# PIC16F877_board.net
KiCad netlist of a schematic drawn in EAGLE
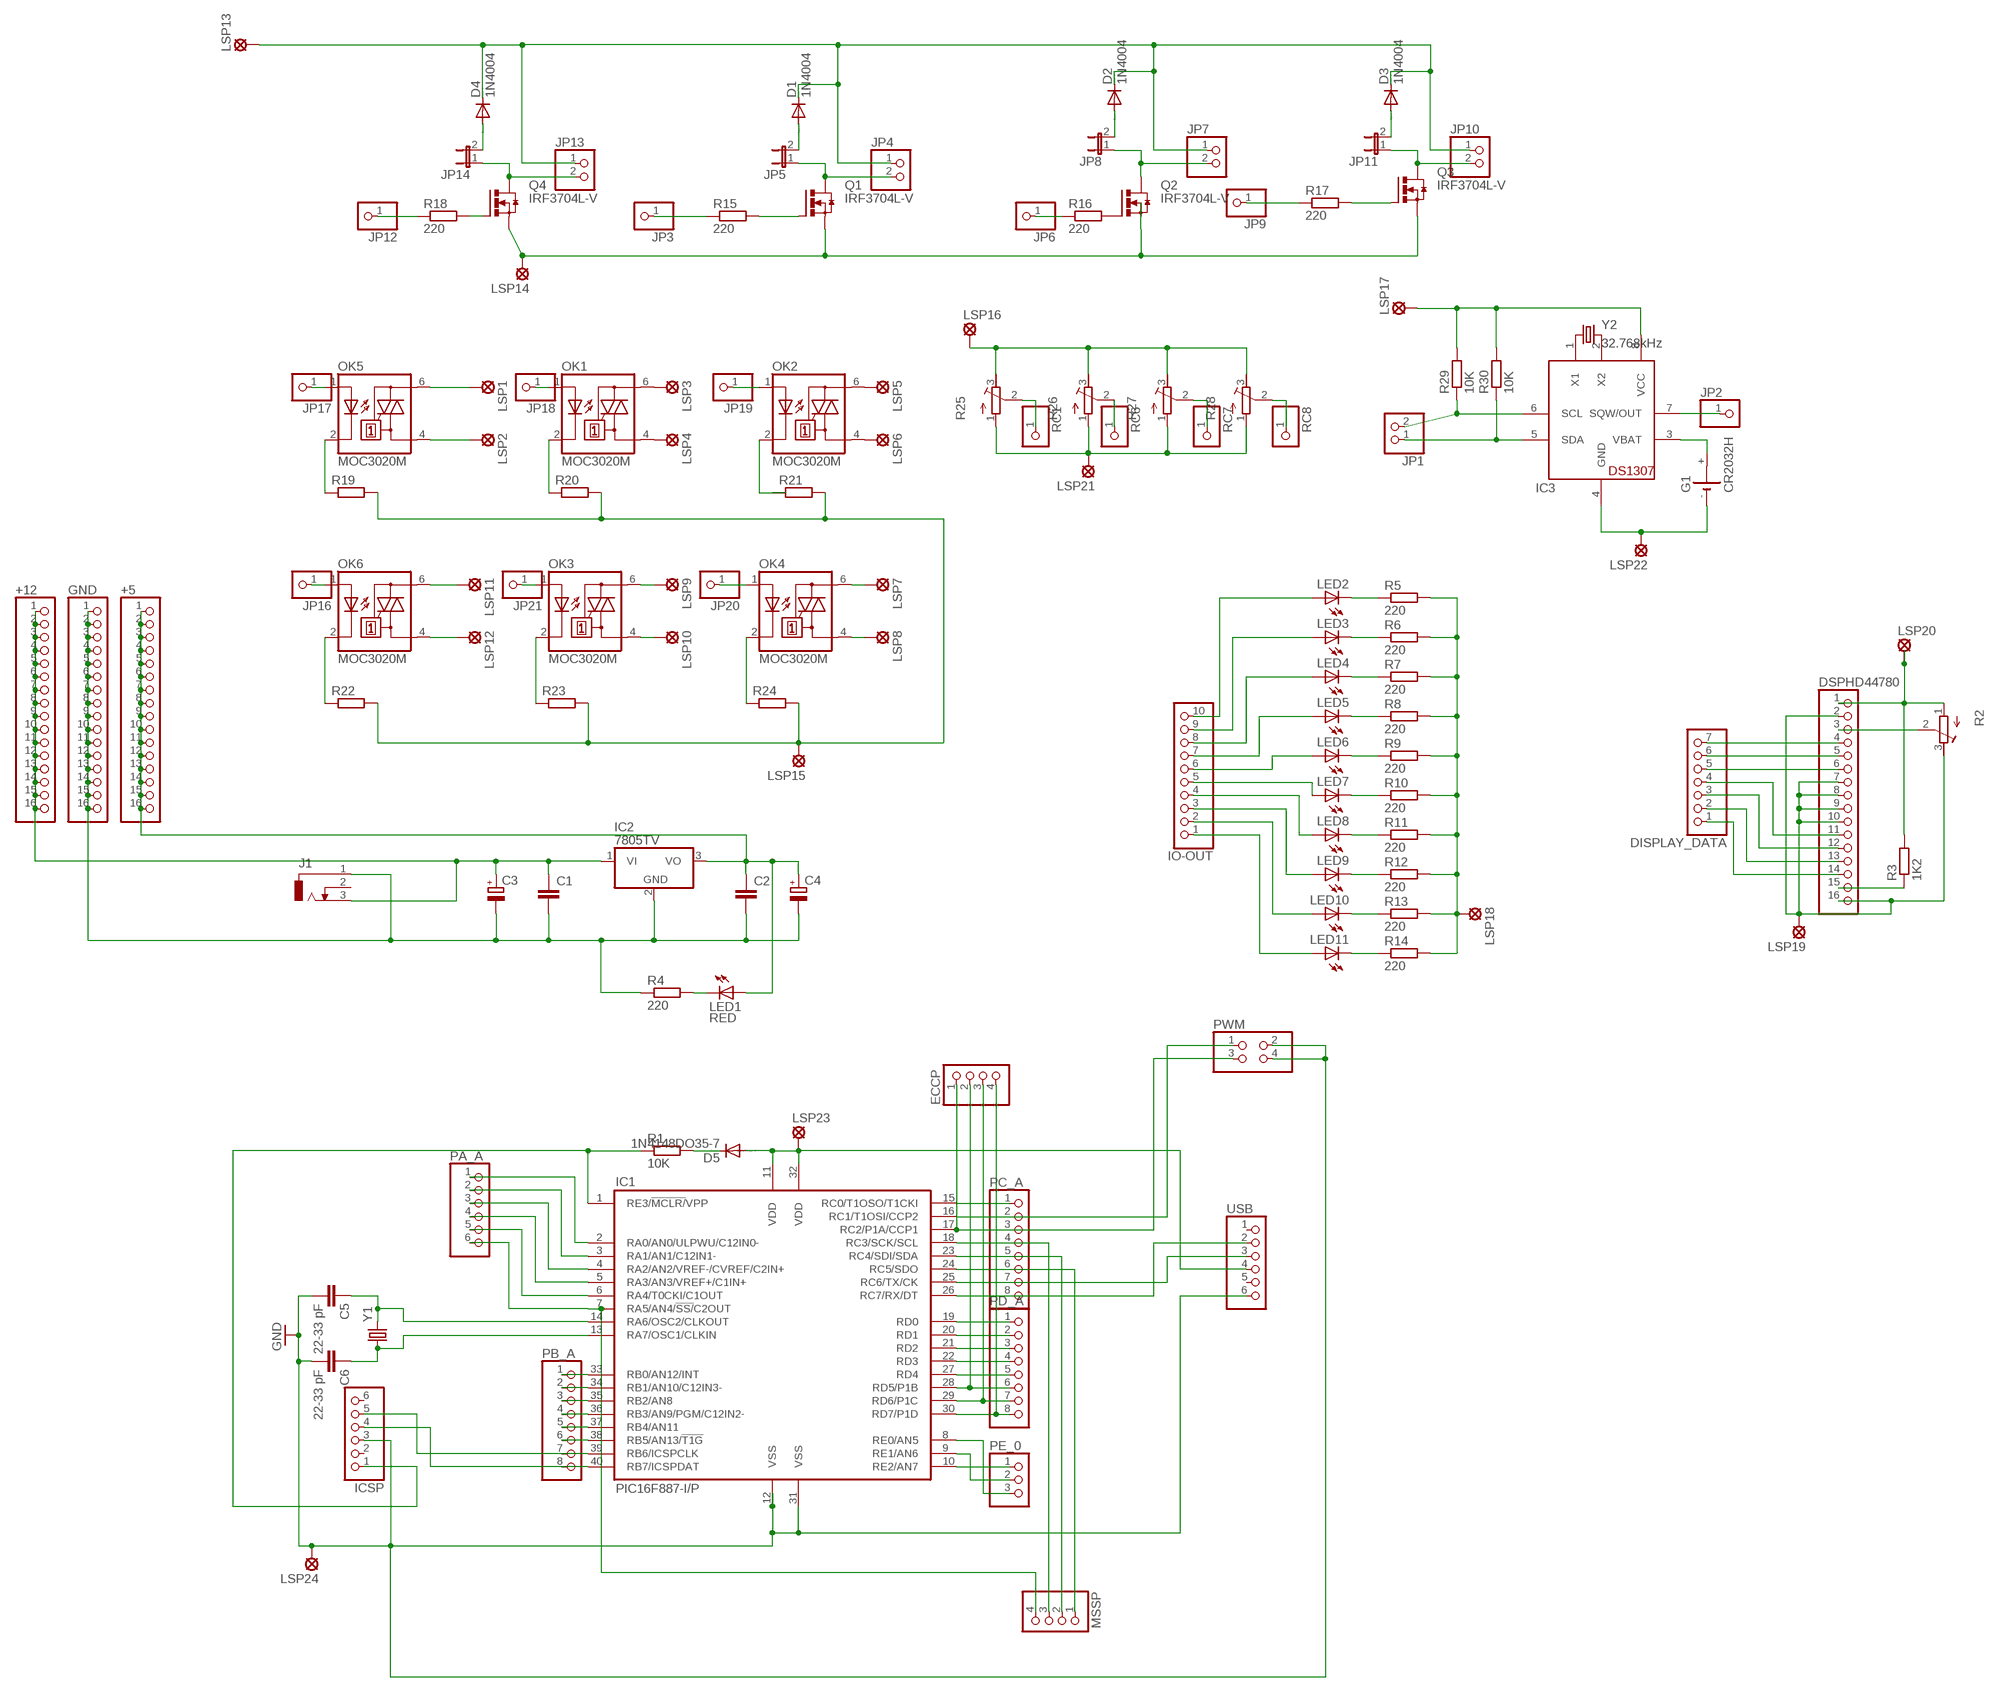
[diagram p0: schematic, sheet 1]

(export (version "E")
  (design (tool "Eeschema 10.0.6"))
  (components
    (comp (ref "+5")
      (value "PINHD-1X16")
      (footprint "eagle-import:1X16")
      (libsource (lib "eagle-import") (part "PINHD-1X16"))
    )
    (comp (ref "+12")
      (value "PINHD-1X16")
      (footprint "eagle-import:1X16")
      (libsource (lib "eagle-import") (part "PINHD-1X16"))
    )
    (comp (ref "C1")
      (value "C-EU050-025X075")
      (footprint "eagle-import:C050-025X075")
      (libsource (lib "eagle-import") (part "resistor_C-EU050-025X075"))
    )
    (comp (ref "C2")
      (value "C-EU050-025X075")
      (footprint "eagle-import:C050-025X075")
      (libsource (lib "eagle-import") (part "resistor_C-EU050-025X075"))
    )
    (comp (ref "C3")
      (value "CPOL-EUE2,5-6E")
      (footprint "eagle-import:E2,5-6E")
      (libsource (lib "eagle-import") (part "CPOL-EUE2,5-6E"))
    )
    (comp (ref "C4")
      (value "CPOL-EUE2,5-6E")
      (footprint "eagle-import:E2,5-6E")
      (libsource (lib "eagle-import") (part "CPOL-EUE2,5-6E"))
    )
    (comp (ref "C5")
      (value "22-33 pF")
      (footprint "eagle-import:C025-024X044")
      (libsource (lib "eagle-import") (part "C-EU025-024X044"))
    )
    (comp (ref "C6")
      (value "22-33 pF")
      (footprint "eagle-import:C025-024X044")
      (libsource (lib "eagle-import") (part "C-EU025-024X044"))
    )
    (comp (ref "D1")
      (value "1N4004")
      (footprint "eagle-import:DO41-10")
      (libsource (lib "eagle-import") (part "1N4004"))
    )
    (comp (ref "D2")
      (value "1N4004")
      (footprint "eagle-import:DO41-10")
      (libsource (lib "eagle-import") (part "1N4004"))
    )
    (comp (ref "D3")
      (value "1N4004")
      (footprint "eagle-import:DO41-10")
      (libsource (lib "eagle-import") (part "1N4004"))
    )
    (comp (ref "D4")
      (value "1N4004")
      (footprint "eagle-import:DO41-10")
      (libsource (lib "eagle-import") (part "1N4004"))
    )
    (comp (ref "D5")
      (value "1N4148DO35-7")
      (footprint "eagle-import:DO35-7")
      (libsource (lib "eagle-import") (part "1N4148DO35-7"))
    )
    (comp (ref "DISPLAY_DATA")
      (value "PINHD-1X7")
      (footprint "eagle-import:1X07")
      (libsource (lib "eagle-import") (part "PINHD-1X7"))
    )
    (comp (ref "DSPHD44780")
      (value "PINHD-1X16")
      (footprint "eagle-import:1X16")
      (libsource (lib "eagle-import") (part "PINHD-1X16"))
    )
    (comp (ref "ECCP")
      (value "PINHD-1X4")
      (footprint "eagle-import:1X04")
      (libsource (lib "eagle-import") (part "PINHD-1X4"))
    )
    (comp (ref "G1")
      (value "CR2032H")
      (footprint "eagle-import:CR2032H")
      (libsource (lib "eagle-import") (part "CR2032H"))
    )
    (comp (ref "GND")
      (value "PINHD-1X16")
      (footprint "eagle-import:1X16")
      (libsource (lib "eagle-import") (part "PINHD-1X16"))
    )
    (comp (ref "IC1")
      (value "PIC16F887-I/P")
      (footprint "eagle-import:DIL40")
      (libsource (lib "eagle-import") (part "PIC16F887-I/P"))
    )
    (comp (ref "IC2")
      (value "7805TV")
      (footprint "eagle-import:TO220V")
      (libsource (lib "eagle-import") (part "78TV05"))
    )
    (comp (ref "IC3")
      (value "DS1307")
      (footprint "eagle-import:DIL08")
      (libsource (lib "eagle-import") (part "DS1307"))
    )
    (comp (ref "ICSP")
      (value "PINHD-1X6")
      (footprint "eagle-import:1X06")
      (libsource (lib "eagle-import") (part "PINHD-1X6"))
    )
    (comp (ref "IO-OUT")
      (value "PINHD-1X10")
      (footprint "eagle-import:1X10")
      (libsource (lib "eagle-import") (part "PINHD-1X10"))
    )
    (comp (ref "J1")
      (value "DCJ0303")
      (footprint "eagle-import:DCJ0303")
      (libsource (lib "eagle-import") (part "DCJ0303"))
    )
    (comp (ref "JP1")
      (value "PINHD-1X2")
      (footprint "eagle-import:1X02")
      (libsource (lib "eagle-import") (part "PINHD-1X2"))
    )
    (comp (ref "JP2")
      (value "PINHD-1X1")
      (footprint "eagle-import:1X01")
      (libsource (lib "eagle-import") (part "PINHD-1X1"))
    )
    (comp (ref "JP3")
      (value "PINHD-1X1")
      (footprint "eagle-import:1X01")
      (libsource (lib "eagle-import") (part "PINHD-1X1"))
    )
    (comp (ref "JP4")
      (value "PINHD-1X2")
      (footprint "eagle-import:1X02")
      (libsource (lib "eagle-import") (part "PINHD-1X2"))
    )
    (comp (ref "JP5")
      (value "JP1E")
      (footprint "eagle-import:JP1")
      (libsource (lib "eagle-import") (part "JP1E"))
    )
    (comp (ref "JP6")
      (value "PINHD-1X1")
      (footprint "eagle-import:1X01")
      (libsource (lib "eagle-import") (part "PINHD-1X1"))
    )
    (comp (ref "JP7")
      (value "PINHD-1X2")
      (footprint "eagle-import:1X02")
      (libsource (lib "eagle-import") (part "PINHD-1X2"))
    )
    (comp (ref "JP8")
      (value "JP1E")
      (footprint "eagle-import:JP1")
      (libsource (lib "eagle-import") (part "JP1E"))
    )
    (comp (ref "JP9")
      (value "PINHD-1X1")
      (footprint "eagle-import:1X01")
      (libsource (lib "eagle-import") (part "PINHD-1X1"))
    )
    (comp (ref "JP10")
      (value "PINHD-1X2")
      (footprint "eagle-import:1X02")
      (libsource (lib "eagle-import") (part "PINHD-1X2"))
    )
    (comp (ref "JP11")
      (value "JP1E")
      (footprint "eagle-import:JP1")
      (libsource (lib "eagle-import") (part "JP1E"))
    )
    (comp (ref "JP12")
      (value "PINHD-1X1")
      (footprint "eagle-import:1X01")
      (libsource (lib "eagle-import") (part "PINHD-1X1"))
    )
    (comp (ref "JP13")
      (value "PINHD-1X2")
      (footprint "eagle-import:1X02")
      (libsource (lib "eagle-import") (part "PINHD-1X2"))
    )
    (comp (ref "JP14")
      (value "JP1E")
      (footprint "eagle-import:JP1")
      (libsource (lib "eagle-import") (part "JP1E"))
    )
    (comp (ref "JP16")
      (value "PINHD-1X1")
      (footprint "eagle-import:1X01")
      (libsource (lib "eagle-import") (part "PINHD-1X1"))
    )
    (comp (ref "JP17")
      (value "PINHD-1X1")
      (footprint "eagle-import:1X01")
      (libsource (lib "eagle-import") (part "PINHD-1X1"))
    )
    (comp (ref "JP18")
      (value "PINHD-1X1")
      (footprint "eagle-import:1X01")
      (libsource (lib "eagle-import") (part "PINHD-1X1"))
    )
    (comp (ref "JP19")
      (value "PINHD-1X1")
      (footprint "eagle-import:1X01")
      (libsource (lib "eagle-import") (part "PINHD-1X1"))
    )
    (comp (ref "JP20")
      (value "PINHD-1X1")
      (footprint "eagle-import:1X01")
      (libsource (lib "eagle-import") (part "PINHD-1X1"))
    )
    (comp (ref "JP21")
      (value "PINHD-1X1")
      (footprint "eagle-import:1X01")
      (libsource (lib "eagle-import") (part "PINHD-1X1"))
    )
    (comp (ref "LED1")
      (value "RED")
      (footprint "eagle-import:LED5MM")
      (libsource (lib "eagle-import") (part "LED5MM"))
    )
    (comp (ref "LED2")
      (value "LED3MM")
      (footprint "eagle-import:LED3MM")
      (libsource (lib "eagle-import") (part "LED3MM"))
    )
    (comp (ref "LED3")
      (value "LED3MM")
      (footprint "eagle-import:LED3MM")
      (libsource (lib "eagle-import") (part "LED3MM"))
    )
    (comp (ref "LED4")
      (value "LED3MM")
      (footprint "eagle-import:LED3MM")
      (libsource (lib "eagle-import") (part "LED3MM"))
    )
    (comp (ref "LED5")
      (value "LED3MM")
      (footprint "eagle-import:LED3MM")
      (libsource (lib "eagle-import") (part "LED3MM"))
    )
    (comp (ref "LED6")
      (value "LED3MM")
      (footprint "eagle-import:LED3MM")
      (libsource (lib "eagle-import") (part "LED3MM"))
    )
    (comp (ref "LED7")
      (value "LED3MM")
      (footprint "eagle-import:LED3MM")
      (libsource (lib "eagle-import") (part "LED3MM"))
    )
    (comp (ref "LED8")
      (value "LED3MM")
      (footprint "eagle-import:LED3MM")
      (libsource (lib "eagle-import") (part "LED3MM"))
    )
    (comp (ref "LED9")
      (value "LED3MM")
      (footprint "eagle-import:LED3MM")
      (libsource (lib "eagle-import") (part "LED3MM"))
    )
    (comp (ref "LED10")
      (value "LED3MM")
      (footprint "eagle-import:LED3MM")
      (libsource (lib "eagle-import") (part "LED3MM"))
    )
    (comp (ref "LED11")
      (value "LED3MM")
      (footprint "eagle-import:LED3MM")
      (libsource (lib "eagle-import") (part "LED3MM"))
    )
    (comp (ref "LSP1")
      (value "LSP10")
      (footprint "eagle-import:LSP10")
      (libsource (lib "eagle-import") (part "LSP10"))
    )
    (comp (ref "LSP2")
      (value "LSP10")
      (footprint "eagle-import:LSP10")
      (libsource (lib "eagle-import") (part "LSP10"))
    )
    (comp (ref "LSP3")
      (value "LSP10")
      (footprint "eagle-import:LSP10")
      (libsource (lib "eagle-import") (part "LSP10"))
    )
    (comp (ref "LSP4")
      (value "LSP10")
      (footprint "eagle-import:LSP10")
      (libsource (lib "eagle-import") (part "LSP10"))
    )
    (comp (ref "LSP5")
      (value "LSP10")
      (footprint "eagle-import:LSP10")
      (libsource (lib "eagle-import") (part "LSP10"))
    )
    (comp (ref "LSP6")
      (value "LSP10")
      (footprint "eagle-import:LSP10")
      (libsource (lib "eagle-import") (part "LSP10"))
    )
    (comp (ref "LSP7")
      (value "LSP10")
      (footprint "eagle-import:LSP10")
      (libsource (lib "eagle-import") (part "LSP10"))
    )
    (comp (ref "LSP8")
      (value "LSP10")
      (footprint "eagle-import:LSP10")
      (libsource (lib "eagle-import") (part "LSP10"))
    )
    (comp (ref "LSP9")
      (value "LSP10")
      (footprint "eagle-import:LSP10")
      (libsource (lib "eagle-import") (part "LSP10"))
    )
    (comp (ref "LSP10")
      (value "LSP10")
      (footprint "eagle-import:LSP10")
      (libsource (lib "eagle-import") (part "LSP10"))
    )
    (comp (ref "LSP11")
      (value "LSP10")
      (footprint "eagle-import:LSP10")
      (libsource (lib "eagle-import") (part "LSP10"))
    )
    (comp (ref "LSP12")
      (value "LSP10")
      (footprint "eagle-import:LSP10")
      (libsource (lib "eagle-import") (part "LSP10"))
    )
    (comp (ref "LSP13")
      (value "LSP10")
      (footprint "eagle-import:LSP10")
      (libsource (lib "eagle-import") (part "LSP10"))
    )
    (comp (ref "LSP14")
      (value "LSP10")
      (footprint "eagle-import:LSP10")
      (libsource (lib "eagle-import") (part "LSP10"))
    )
    (comp (ref "LSP15")
      (value "LSP10")
      (footprint "eagle-import:LSP10")
      (libsource (lib "eagle-import") (part "LSP10"))
    )
    (comp (ref "LSP16")
      (value "LSP10")
      (footprint "eagle-import:LSP10")
      (libsource (lib "eagle-import") (part "LSP10"))
    )
    (comp (ref "LSP17")
      (value "LSP10")
      (footprint "eagle-import:LSP10")
      (libsource (lib "eagle-import") (part "LSP10"))
    )
    (comp (ref "LSP18")
      (value "LSP10")
      (footprint "eagle-import:LSP10")
      (libsource (lib "eagle-import") (part "LSP10"))
    )
    (comp (ref "LSP19")
      (value "LSP10")
      (footprint "eagle-import:LSP10")
      (libsource (lib "eagle-import") (part "LSP10"))
    )
    (comp (ref "LSP20")
      (value "LSP10")
      (footprint "eagle-import:LSP10")
      (libsource (lib "eagle-import") (part "LSP10"))
    )
    (comp (ref "LSP21")
      (value "LSP10")
      (footprint "eagle-import:LSP10")
      (libsource (lib "eagle-import") (part "LSP10"))
    )
    (comp (ref "LSP22")
      (value "LSP10")
      (footprint "eagle-import:LSP10")
      (libsource (lib "eagle-import") (part "LSP10"))
    )
    (comp (ref "LSP23")
      (value "LSP10")
      (footprint "eagle-import:LSP10")
      (libsource (lib "eagle-import") (part "LSP10"))
    )
    (comp (ref "LSP24")
      (value "LSP10")
      (footprint "eagle-import:LSP10")
      (libsource (lib "eagle-import") (part "LSP10"))
    )
    (comp (ref "MSSP")
      (value "PINHD-1X4")
      (footprint "eagle-import:1X04")
      (libsource (lib "eagle-import") (part "PINHD-1X4"))
    )
    (comp (ref "OK1")
      (value "MOC3020M")
      (footprint "eagle-import:DIL06")
      (fields (field (name "MF") "FAIRCHILD SEMICONDUCTOR") (field (name "MPN") "MOC3020-M"))
      (libsource (lib "eagle-import") (part "MOC30M20"))
    )
    (comp (ref "OK2")
      (value "MOC3020M")
      (footprint "eagle-import:DIL06")
      (fields (field (name "MF") "FAIRCHILD SEMICONDUCTOR") (field (name "MPN") "MOC3020-M"))
      (libsource (lib "eagle-import") (part "MOC30M20"))
    )
    (comp (ref "OK3")
      (value "MOC3020M")
      (footprint "eagle-import:DIL06")
      (fields (field (name "MF") "FAIRCHILD SEMICONDUCTOR") (field (name "MPN") "MOC3020-M"))
      (libsource (lib "eagle-import") (part "MOC30M20"))
    )
    (comp (ref "OK4")
      (value "MOC3020M")
      (footprint "eagle-import:DIL06")
      (fields (field (name "MF") "FAIRCHILD SEMICONDUCTOR") (field (name "MPN") "MOC3020-M"))
      (libsource (lib "eagle-import") (part "MOC30M20"))
    )
    (comp (ref "OK5")
      (value "MOC3020M")
      (footprint "eagle-import:DIL06")
      (fields (field (name "MF") "FAIRCHILD SEMICONDUCTOR") (field (name "MPN") "MOC3020-M"))
      (libsource (lib "eagle-import") (part "MOC30M20"))
    )
    (comp (ref "OK6")
      (value "MOC3020M")
      (footprint "eagle-import:DIL06")
      (fields (field (name "MF") "FAIRCHILD SEMICONDUCTOR") (field (name "MPN") "MOC3020-M"))
      (libsource (lib "eagle-import") (part "MOC30M20"))
    )
    (comp (ref "PA_A")
      (value "PINHD-1X6")
      (footprint "eagle-import:1X06")
      (libsource (lib "eagle-import") (part "PINHD-1X6"))
    )
    (comp (ref "PB_A")
      (value "PINHD-1X8")
      (footprint "eagle-import:1X08")
      (libsource (lib "eagle-import") (part "PINHD-1X8"))
    )
    (comp (ref "PC_A")
      (value "PINHD-1X8")
      (footprint "eagle-import:1X08")
      (libsource (lib "eagle-import") (part "PINHD-1X8"))
    )
    (comp (ref "PD_A")
      (value "PINHD-1X8")
      (footprint "eagle-import:1X08")
      (libsource (lib "eagle-import") (part "PINHD-1X8"))
    )
    (comp (ref "PE_0")
      (value "PINHD-1X3")
      (footprint "eagle-import:1X03")
      (libsource (lib "eagle-import") (part "PINHD-1X3"))
    )
    (comp (ref "PWM")
      (value "PINHD-2X2")
      (footprint "eagle-import:2X02")
      (libsource (lib "eagle-import") (part "PINHD-2X2"))
    )
    (comp (ref "Q1")
      (value "IRF3704L-V")
      (footprint "eagle-import:TO262-V")
      (libsource (lib "eagle-import") (part "IRF3704L-V"))
    )
    (comp (ref "Q2")
      (value "IRF3704L-V")
      (footprint "eagle-import:TO262-V")
      (libsource (lib "eagle-import") (part "IRF3704L-V"))
    )
    (comp (ref "Q3")
      (value "IRF3704L-V")
      (footprint "eagle-import:TO262-V")
      (libsource (lib "eagle-import") (part "IRF3704L-V"))
    )
    (comp (ref "Q4")
      (value "IRF3704L-V")
      (footprint "eagle-import:TO262-V")
      (libsource (lib "eagle-import") (part "IRF3704L-V"))
    )
    (comp (ref "R1")
      (value "10K")
      (footprint "eagle-import:0207_10")
      (libsource (lib "eagle-import") (part "resistor_R-EU_0207/10"))
    )
    (comp (ref "R2")
      (value "R-TRIMM3339P")
      (footprint "eagle-import:RTRIM3339P")
      (libsource (lib "eagle-import") (part "R-TRIMM3339P"))
    )
    (comp (ref "R3")
      (value "1K2")
      (footprint "eagle-import:0207_10")
      (libsource (lib "eagle-import") (part "resistor_R-EU_0207/10"))
    )
    (comp (ref "R4")
      (value "220")
      (footprint "eagle-import:0207_10")
      (libsource (lib "eagle-import") (part "resistor_R-EU_0207/10"))
    )
    (comp (ref "R5")
      (value "220")
      (footprint "eagle-import:0207_10")
      (libsource (lib "eagle-import") (part "R-EU_0207/10"))
    )
    (comp (ref "R6")
      (value "220")
      (footprint "eagle-import:0207_10")
      (libsource (lib "eagle-import") (part "R-EU_0207/10"))
    )
    (comp (ref "R7")
      (value "220")
      (footprint "eagle-import:0207_10")
      (libsource (lib "eagle-import") (part "R-EU_0207/10"))
    )
    (comp (ref "R8")
      (value "220")
      (footprint "eagle-import:0207_10")
      (libsource (lib "eagle-import") (part "R-EU_0207/10"))
    )
    (comp (ref "R9")
      (value "220")
      (footprint "eagle-import:0207_10")
      (libsource (lib "eagle-import") (part "R-EU_0207/10"))
    )
    (comp (ref "R10")
      (value "220")
      (footprint "eagle-import:0207_10")
      (libsource (lib "eagle-import") (part "R-EU_0207/10"))
    )
    (comp (ref "R11")
      (value "220")
      (footprint "eagle-import:0207_10")
      (libsource (lib "eagle-import") (part "R-EU_0207/10"))
    )
    (comp (ref "R12")
      (value "220")
      (footprint "eagle-import:0207_10")
      (libsource (lib "eagle-import") (part "R-EU_0207/10"))
    )
    (comp (ref "R13")
      (value "220")
      (footprint "eagle-import:0207_10")
      (libsource (lib "eagle-import") (part "R-EU_0207/10"))
    )
    (comp (ref "R14")
      (value "220")
      (footprint "eagle-import:0207_10")
      (libsource (lib "eagle-import") (part "R-EU_0207/10"))
    )
    (comp (ref "R15")
      (value "220")
      (footprint "eagle-import:0207_10")
      (libsource (lib "eagle-import") (part "R-EU_0207/10"))
    )
    (comp (ref "R16")
      (value "220")
      (footprint "eagle-import:0207_10")
      (libsource (lib "eagle-import") (part "R-EU_0207/10"))
    )
    (comp (ref "R17")
      (value "220")
      (footprint "eagle-import:0207_10")
      (libsource (lib "eagle-import") (part "R-EU_0207/10"))
    )
    (comp (ref "R18")
      (value "220")
      (footprint "eagle-import:0207_10")
      (libsource (lib "eagle-import") (part "R-EU_0207/10"))
    )
    (comp (ref "R19")
      (value "R-EU_0207/10")
      (footprint "eagle-import:0207_10")
      (libsource (lib "eagle-import") (part "resistor_R-EU_0207/10"))
    )
    (comp (ref "R20")
      (value "R-EU_0207/10")
      (footprint "eagle-import:0207_10")
      (libsource (lib "eagle-import") (part "resistor_R-EU_0207/10"))
    )
    (comp (ref "R21")
      (value "R-EU_0207/10")
      (footprint "eagle-import:0207_10")
      (libsource (lib "eagle-import") (part "resistor_R-EU_0207/10"))
    )
    (comp (ref "R22")
      (value "R-EU_0207/10")
      (footprint "eagle-import:0207_10")
      (libsource (lib "eagle-import") (part "resistor_R-EU_0207/10"))
    )
    (comp (ref "R23")
      (value "R-EU_0207/10")
      (footprint "eagle-import:0207_10")
      (libsource (lib "eagle-import") (part "resistor_R-EU_0207/10"))
    )
    (comp (ref "R24")
      (value "R-EU_0207/10")
      (footprint "eagle-import:0207_10")
      (libsource (lib "eagle-import") (part "resistor_R-EU_0207/10"))
    )
    (comp (ref "R25")
      (value "R-TRIMM3339P")
      (footprint "eagle-import:RTRIM3339P")
      (libsource (lib "eagle-import") (part "resistor_R-TRIMM3339P"))
    )
    (comp (ref "R26")
      (value "R-TRIMM3339P")
      (footprint "eagle-import:RTRIM3339P")
      (libsource (lib "eagle-import") (part "resistor_R-TRIMM3339P"))
    )
    (comp (ref "R27")
      (value "R-TRIMM3339P")
      (footprint "eagle-import:RTRIM3339P")
      (libsource (lib "eagle-import") (part "resistor_R-TRIMM3339P"))
    )
    (comp (ref "R28")
      (value "R-TRIMM3339P")
      (footprint "eagle-import:RTRIM3339P")
      (libsource (lib "eagle-import") (part "resistor_R-TRIMM3339P"))
    )
    (comp (ref "R29")
      (value "10K")
      (footprint "eagle-import:0207_10")
      (libsource (lib "eagle-import") (part "resistor_R-EU_0207/10"))
    )
    (comp (ref "R30")
      (value "10K")
      (footprint "eagle-import:0207_10")
      (libsource (lib "eagle-import") (part "resistor_R-EU_0207/10"))
    )
    (comp (ref "RC1")
      (value "PINHD-1X1")
      (footprint "eagle-import:1X01")
      (libsource (lib "eagle-import") (part "PINHD-1X1"))
    )
    (comp (ref "RC6")
      (value "PINHD-1X1")
      (footprint "eagle-import:1X01")
      (libsource (lib "eagle-import") (part "PINHD-1X1"))
    )
    (comp (ref "RC7")
      (value "PINHD-1X1")
      (footprint "eagle-import:1X01")
      (libsource (lib "eagle-import") (part "PINHD-1X1"))
    )
    (comp (ref "RC8")
      (value "PINHD-1X1")
      (footprint "eagle-import:1X01")
      (libsource (lib "eagle-import") (part "PINHD-1X1"))
    )
    (comp (ref "USB")
      (value "PINHD-1X6")
      (footprint "eagle-import:1X06")
      (libsource (lib "eagle-import") (part "PINHD-1X6"))
    )
    (comp (ref "Y1")
      (value "CRYSTALHC49UV")
      (footprint "eagle-import:HC49U-V")
      (libsource (lib "eagle-import") (part "CRYSTALHC49UV"))
    )
    (comp (ref "Y2")
      (value "32.768kHz")
      (footprint "eagle-import:TC26V")
      (libsource (lib "eagle-import") (part "CRYSTALTC26V"))
    )
  )
  (nets
    (net (code "1") (name "GND") (class "Default")
      (node (ref "C5") (pin "2") (pinfunction "2_2") (pintype "passive"))
      (node (ref "C6") (pin "2") (pinfunction "2_2") (pintype "passive"))
      (node (ref "IC1") (pin "12") (pinfunction "VSS_12") (pintype "power_in"))
      (node (ref "IC1") (pin "31") (pinfunction "VSS_31") (pintype "power_in"))
      (node (ref "ICSP") (pin "3") (pinfunction "3_3") (pintype "passive"))
      (node (ref "LSP24") (pin "MP") (pinfunction "MP_MP") (pintype "passive"))
      (node (ref "PWM") (pin "2") (pinfunction "2_2") (pintype "passive"))
      (node (ref "PWM") (pin "4") (pinfunction "4_4") (pintype "passive"))
      (node (ref "USB") (pin "6") (pinfunction "6_6") (pintype "passive"))
    )
    (net (code "2") (name "Net-(D1-PadA)") (class "Default")
      (node (ref "D1") (pin "A") (pinfunction "A_A") (pintype "passive"))
      (node (ref "JP5") (pin "2") (pinfunction "2_2") (pintype "passive"))
    )
    (net (code "3") (name "Net-(D1-PadC)") (class "Default")
      (node (ref "D1") (pin "C") (pinfunction "C_C") (pintype "passive"))
      (node (ref "D2") (pin "C") (pinfunction "C_C") (pintype "passive"))
      (node (ref "D3") (pin "C") (pinfunction "C_C") (pintype "passive"))
      (node (ref "D4") (pin "C") (pinfunction "C_C") (pintype "passive"))
      (node (ref "JP10") (pin "1") (pinfunction "1_1") (pintype "passive"))
      (node (ref "JP13") (pin "1") (pinfunction "1_1") (pintype "passive"))
      (node (ref "JP4") (pin "1") (pinfunction "1_1") (pintype "passive"))
      (node (ref "JP7") (pin "1") (pinfunction "1_1") (pintype "passive"))
      (node (ref "LSP13") (pin "MP") (pinfunction "MP_MP") (pintype "passive"))
    )
    (net (code "4") (name "Net-(D2-PadA)") (class "Default")
      (node (ref "D2") (pin "A") (pinfunction "A_A") (pintype "passive"))
      (node (ref "JP8") (pin "2") (pinfunction "2_2") (pintype "passive"))
    )
    (net (code "5") (name "Net-(D3-PadA)") (class "Default")
      (node (ref "D3") (pin "A") (pinfunction "A_A") (pintype "passive"))
      (node (ref "JP11") (pin "2") (pinfunction "2_2") (pintype "passive"))
    )
    (net (code "6") (name "Net-(D4-PadA)") (class "Default")
      (node (ref "D4") (pin "A") (pinfunction "A_A") (pintype "passive"))
      (node (ref "JP14") (pin "2") (pinfunction "2_2") (pintype "passive"))
    )
    (net (code "7") (name "Net-(D5-PadA)") (class "Default")
      (node (ref "D5") (pin "A") (pinfunction "A_A") (pintype "passive"))
      (node (ref "IC1") (pin "11") (pinfunction "VDD_11") (pintype "power_in"))
      (node (ref "IC1") (pin "32") (pinfunction "VDD_32") (pintype "power_in"))
      (node (ref "LSP23") (pin "MP") (pinfunction "MP_MP") (pintype "passive"))
      (node (ref "USB") (pin "4") (pinfunction "4_4") (pintype "passive"))
    )
    (net (code "8") (name "Net-(D5-PadC)") (class "Default")
      (node (ref "D5") (pin "C") (pinfunction "C_C") (pintype "passive"))
      (node (ref "R1") (pin "2") (pinfunction "2_2") (pintype "passive"))
    )
    (net (code "9") (name "Net-(DISPLAY_DATA-Pad1)") (class "Default")
      (node (ref "DISPLAY_DATA") (pin "1") (pinfunction "1_1") (pintype "passive"))
      (node (ref "DSPHD44780") (pin "14") (pinfunction "14_14") (pintype "passive"))
    )
    (net (code "10") (name "Net-(DISPLAY_DATA-Pad2)") (class "Default")
      (node (ref "DISPLAY_DATA") (pin "2") (pinfunction "2_2") (pintype "passive"))
      (node (ref "DSPHD44780") (pin "13") (pinfunction "13_13") (pintype "passive"))
    )
    (net (code "11") (name "Net-(DISPLAY_DATA-Pad3)") (class "Default")
      (node (ref "DISPLAY_DATA") (pin "3") (pinfunction "3_3") (pintype "passive"))
      (node (ref "DSPHD44780") (pin "12") (pinfunction "12_12") (pintype "passive"))
    )
    (net (code "12") (name "Net-(DISPLAY_DATA-Pad4)") (class "Default")
      (node (ref "DISPLAY_DATA") (pin "4") (pinfunction "4_4") (pintype "passive"))
      (node (ref "DSPHD44780") (pin "11") (pinfunction "11_11") (pintype "passive"))
    )
    (net (code "13") (name "Net-(DISPLAY_DATA-Pad5)") (class "Default")
      (node (ref "DISPLAY_DATA") (pin "5") (pinfunction "5_5") (pintype "passive"))
      (node (ref "DSPHD44780") (pin "6") (pinfunction "6_6") (pintype "passive"))
    )
    (net (code "14") (name "Net-(DISPLAY_DATA-Pad6)") (class "Default")
      (node (ref "DISPLAY_DATA") (pin "6") (pinfunction "6_6") (pintype "passive"))
      (node (ref "DSPHD44780") (pin "5") (pinfunction "5_5") (pintype "passive"))
    )
    (net (code "15") (name "Net-(DISPLAY_DATA-Pad7)") (class "Default")
      (node (ref "DISPLAY_DATA") (pin "7") (pinfunction "7_7") (pintype "passive"))
      (node (ref "DSPHD44780") (pin "4") (pinfunction "4_4") (pintype "passive"))
    )
    (net (code "16") (name "Net-(DSPHD44780-Pad15)") (class "Default")
      (node (ref "DSPHD44780") (pin "15") (pinfunction "15_15") (pintype "passive"))
      (node (ref "R3") (pin "1") (pinfunction "1_1") (pintype "passive"))
    )
    (net (code "17") (name "Net-(IC1-RA0{slash}AN0{slash}ULPWU{slash}C12IN0-)") (class "Default")
      (node (ref "IC1") (pin "2") (pinfunction "RA0/AN0/ULPWU/C12IN0-_2") (pintype "bidirectional"))
      (node (ref "PA_A") (pin "1") (pinfunction "1_1") (pintype "passive"))
    )
    (net (code "18") (name "Net-(IC1-RA1{slash}AN1{slash}C12IN1-)") (class "Default")
      (node (ref "IC1") (pin "3") (pinfunction "RA1/AN1/C12IN1-_3") (pintype "bidirectional"))
      (node (ref "PA_A") (pin "2") (pinfunction "2_2") (pintype "passive"))
    )
    (net (code "19") (name "Net-(IC1-RA2{slash}AN2{slash}VREF-{slash}CVREF{slash}C2IN+)") (class "Default")
      (node (ref "IC1") (pin "4") (pinfunction "RA2/AN2/VREF-/CVREF/C2IN+_4") (pintype "bidirectional"))
      (node (ref "PA_A") (pin "3") (pinfunction "3_3") (pintype "passive"))
    )
    (net (code "20") (name "Net-(IC1-RA3{slash}AN3{slash}VREF+{slash}C1IN+)") (class "Default")
      (node (ref "IC1") (pin "5") (pinfunction "RA3/AN3/VREF+/C1IN+_5") (pintype "bidirectional"))
      (node (ref "PA_A") (pin "4") (pinfunction "4_4") (pintype "passive"))
    )
    (net (code "21") (name "Net-(IC1-RA4{slash}T0CKI{slash}C1OUT)") (class "Default")
      (node (ref "IC1") (pin "6") (pinfunction "RA4/T0CKI/C1OUT_6") (pintype "bidirectional"))
      (node (ref "PA_A") (pin "5") (pinfunction "5_5") (pintype "passive"))
    )
    (net (code "22") (name "Net-(IC1-RA5{slash}AN4{slash}~{SS{slash}}C2OUT)") (class "Default")
      (node (ref "IC1") (pin "7") (pinfunction "RA5/AN4/~{SS/}C2OUT_7") (pintype "bidirectional"))
      (node (ref "MSSP") (pin "4") (pinfunction "4_4") (pintype "passive"))
      (node (ref "PA_A") (pin "6") (pinfunction "6_6") (pintype "passive"))
    )
    (net (code "23") (name "Net-(IC1-RA6{slash}OSC2{slash}CLKOUT)") (class "Default")
      (node (ref "C5") (pin "1") (pinfunction "1_1") (pintype "passive"))
      (node (ref "IC1") (pin "14") (pinfunction "RA6/OSC2/CLKOUT_14") (pintype "bidirectional"))
      (node (ref "Y1") (pin "2") (pinfunction "2_2") (pintype "passive"))
    )
    (net (code "24") (name "Net-(IC1-RA7{slash}OSC1{slash}CLKIN)") (class "Default")
      (node (ref "C6") (pin "1") (pinfunction "1_1") (pintype "passive"))
      (node (ref "IC1") (pin "13") (pinfunction "RA7/OSC1/CLKIN_13") (pintype "bidirectional"))
      (node (ref "Y1") (pin "1") (pinfunction "1_1") (pintype "passive"))
    )
    (net (code "25") (name "Net-(IC1-RB0{slash}AN12{slash}INT)") (class "Default")
      (node (ref "IC1") (pin "33") (pinfunction "RB0/AN12/INT_33") (pintype "bidirectional"))
      (node (ref "PB_A") (pin "1") (pinfunction "1_1") (pintype "passive"))
    )
    (net (code "26") (name "Net-(IC1-RB1{slash}AN10{slash}C12IN3-)") (class "Default")
      (node (ref "IC1") (pin "34") (pinfunction "RB1/AN10/C12IN3-_34") (pintype "bidirectional"))
      (node (ref "PB_A") (pin "2") (pinfunction "2_2") (pintype "passive"))
    )
    (net (code "27") (name "Net-(IC1-RB2{slash}AN8)") (class "Default")
      (node (ref "IC1") (pin "35") (pinfunction "RB2/AN8_35") (pintype "bidirectional"))
      (node (ref "PB_A") (pin "3") (pinfunction "3_3") (pintype "passive"))
    )
    (net (code "28") (name "Net-(IC1-RB3{slash}AN9{slash}PGM{slash}C12IN2-)") (class "Default")
      (node (ref "IC1") (pin "36") (pinfunction "RB3/AN9/PGM/C12IN2-_36") (pintype "bidirectional"))
      (node (ref "PB_A") (pin "4") (pinfunction "4_4") (pintype "passive"))
    )
    (net (code "29") (name "Net-(IC1-RB4{slash}AN11)") (class "Default")
      (node (ref "IC1") (pin "37") (pinfunction "RB4/AN11_37") (pintype "bidirectional"))
      (node (ref "PB_A") (pin "5") (pinfunction "5_5") (pintype "passive"))
    )
    (net (code "30") (name "Net-(IC1-RB5{slash}AN13{slash}~{T1G})") (class "Default")
      (node (ref "IC1") (pin "38") (pinfunction "RB5/AN13/~{T1G}_38") (pintype "bidirectional"))
      (node (ref "PB_A") (pin "6") (pinfunction "6_6") (pintype "passive"))
    )
    (net (code "31") (name "Net-(IC1-RB6{slash}ICSPCLK)") (class "Default")
      (node (ref "IC1") (pin "39") (pinfunction "RB6/ICSPCLK_39") (pintype "bidirectional"))
      (node (ref "ICSP") (pin "5") (pinfunction "5_5") (pintype "passive"))
      (node (ref "PB_A") (pin "7") (pinfunction "7_7") (pintype "passive"))
    )
    (net (code "32") (name "Net-(IC1-RB7{slash}ICSPDAT)") (class "Default")
      (node (ref "IC1") (pin "40") (pinfunction "RB7/ICSPDAT_40") (pintype "bidirectional"))
      (node (ref "ICSP") (pin "4") (pinfunction "4_4") (pintype "passive"))
      (node (ref "PB_A") (pin "8") (pinfunction "8_8") (pintype "passive"))
    )
    (net (code "33") (name "Net-(IC1-RC0{slash}T1OSO{slash}T1CKI)") (class "Default")
      (node (ref "IC1") (pin "15") (pinfunction "RC0/T1OSO/T1CKI_15") (pintype "bidirectional"))
      (node (ref "PC_A") (pin "1") (pinfunction "1_1") (pintype "passive"))
    )
    (net (code "34") (name "Net-(IC1-RC1{slash}T1OSI{slash}CCP2)") (class "Default")
      (node (ref "IC1") (pin "16") (pinfunction "RC1/T1OSI/CCP2_16") (pintype "bidirectional"))
      (node (ref "PC_A") (pin "2") (pinfunction "2_2") (pintype "passive"))
      (node (ref "PWM") (pin "1") (pinfunction "1_1") (pintype "passive"))
    )
    (net (code "35") (name "Net-(IC1-RC2{slash}P1A{slash}CCP1)") (class "Default")
      (node (ref "ECCP") (pin "1") (pinfunction "1_1") (pintype "passive"))
      (node (ref "IC1") (pin "17") (pinfunction "RC2/P1A/CCP1_17") (pintype "bidirectional"))
      (node (ref "PC_A") (pin "3") (pinfunction "3_3") (pintype "passive"))
      (node (ref "PWM") (pin "3") (pinfunction "3_3") (pintype "passive"))
    )
    (net (code "36") (name "Net-(IC1-RC3{slash}SCK{slash}SCL)") (class "Default")
      (node (ref "IC1") (pin "18") (pinfunction "RC3/SCK/SCL_18") (pintype "bidirectional"))
      (node (ref "MSSP") (pin "3") (pinfunction "3_3") (pintype "passive"))
      (node (ref "PC_A") (pin "4") (pinfunction "4_4") (pintype "passive"))
    )
    (net (code "37") (name "Net-(IC1-RC4{slash}SDI{slash}SDA)") (class "Default")
      (node (ref "IC1") (pin "23") (pinfunction "RC4/SDI/SDA_23") (pintype "bidirectional"))
      (node (ref "MSSP") (pin "2") (pinfunction "2_2") (pintype "passive"))
      (node (ref "PC_A") (pin "5") (pinfunction "5_5") (pintype "passive"))
    )
    (net (code "38") (name "Net-(IC1-RC5{slash}SDO)") (class "Default")
      (node (ref "IC1") (pin "24") (pinfunction "RC5/SDO_24") (pintype "bidirectional"))
      (node (ref "MSSP") (pin "1") (pinfunction "1_1") (pintype "passive"))
      (node (ref "PC_A") (pin "6") (pinfunction "6_6") (pintype "passive"))
    )
    (net (code "39") (name "Net-(IC1-RC6{slash}TX{slash}CK)") (class "Default")
      (node (ref "IC1") (pin "25") (pinfunction "RC6/TX/CK_25") (pintype "bidirectional"))
      (node (ref "PC_A") (pin "7") (pinfunction "7_7") (pintype "passive"))
      (node (ref "USB") (pin "3") (pinfunction "3_3") (pintype "passive"))
    )
    (net (code "40") (name "Net-(IC1-RC7{slash}RX{slash}DT)") (class "Default")
      (node (ref "IC1") (pin "26") (pinfunction "RC7/RX/DT_26") (pintype "bidirectional"))
      (node (ref "PC_A") (pin "8") (pinfunction "8_8") (pintype "passive"))
      (node (ref "USB") (pin "2") (pinfunction "2_2") (pintype "passive"))
    )
    (net (code "41") (name "Net-(IC1-RD0)") (class "Default")
      (node (ref "IC1") (pin "19") (pinfunction "RD0_19") (pintype "bidirectional"))
      (node (ref "PD_A") (pin "1") (pinfunction "1_1") (pintype "passive"))
    )
    (net (code "42") (name "Net-(IC1-RD1)") (class "Default")
      (node (ref "IC1") (pin "20") (pinfunction "RD1_20") (pintype "bidirectional"))
      (node (ref "PD_A") (pin "2") (pinfunction "2_2") (pintype "passive"))
    )
    (net (code "43") (name "Net-(IC1-RD2)") (class "Default")
      (node (ref "IC1") (pin "21") (pinfunction "RD2_21") (pintype "bidirectional"))
      (node (ref "PD_A") (pin "3") (pinfunction "3_3") (pintype "passive"))
    )
    (net (code "44") (name "Net-(IC1-RD3)") (class "Default")
      (node (ref "IC1") (pin "22") (pinfunction "RD3_22") (pintype "bidirectional"))
      (node (ref "PD_A") (pin "4") (pinfunction "4_4") (pintype "passive"))
    )
    (net (code "45") (name "Net-(IC1-RD4)") (class "Default")
      (node (ref "IC1") (pin "27") (pinfunction "RD4_27") (pintype "bidirectional"))
      (node (ref "PD_A") (pin "5") (pinfunction "5_5") (pintype "passive"))
    )
    (net (code "46") (name "Net-(IC1-RD5{slash}P1B)") (class "Default")
      (node (ref "ECCP") (pin "2") (pinfunction "2_2") (pintype "passive"))
      (node (ref "IC1") (pin "28") (pinfunction "RD5/P1B_28") (pintype "bidirectional"))
      (node (ref "PD_A") (pin "6") (pinfunction "6_6") (pintype "passive"))
    )
    (net (code "47") (name "Net-(IC1-RD6{slash}P1C)") (class "Default")
      (node (ref "ECCP") (pin "3") (pinfunction "3_3") (pintype "passive"))
      (node (ref "IC1") (pin "29") (pinfunction "RD6/P1C_29") (pintype "bidirectional"))
      (node (ref "PD_A") (pin "7") (pinfunction "7_7") (pintype "passive"))
    )
    (net (code "48") (name "Net-(IC1-RD7{slash}P1D)") (class "Default")
      (node (ref "ECCP") (pin "4") (pinfunction "4_4") (pintype "passive"))
      (node (ref "IC1") (pin "30") (pinfunction "RD7/P1D_30") (pintype "bidirectional"))
      (node (ref "PD_A") (pin "8") (pinfunction "8_8") (pintype "passive"))
    )
    (net (code "49") (name "Net-(IC1-RE0{slash}AN5)") (class "Default")
      (node (ref "IC1") (pin "8") (pinfunction "RE0/AN5_8") (pintype "bidirectional"))
      (node (ref "PE_0") (pin "3") (pinfunction "3_3") (pintype "passive"))
    )
    (net (code "50") (name "Net-(IC1-RE1{slash}AN6)") (class "Default")
      (node (ref "IC1") (pin "9") (pinfunction "RE1/AN6_9") (pintype "bidirectional"))
      (node (ref "PE_0") (pin "2") (pinfunction "2_2") (pintype "passive"))
    )
    (net (code "51") (name "Net-(IC1-RE2{slash}AN7)") (class "Default")
      (node (ref "IC1") (pin "10") (pinfunction "RE2/AN7_10") (pintype "bidirectional"))
      (node (ref "PE_0") (pin "1") (pinfunction "1_1") (pintype "passive"))
    )
    (net (code "52") (name "Net-(IC1-RE3{slash}~{MCLR{slash}}VPP)") (class "Default")
      (node (ref "IC1") (pin "1") (pinfunction "RE3/~{MCLR/}VPP_1") (pintype "input"))
      (node (ref "ICSP") (pin "1") (pinfunction "1_1") (pintype "passive"))
      (node (ref "R1") (pin "1") (pinfunction "1_1") (pintype "passive"))
    )
    (net (code "53") (name "Net-(IC2-GND)") (class "Default")
      (node (ref "C1") (pin "2") (pinfunction "2_2") (pintype "passive"))
      (node (ref "C2") (pin "2") (pinfunction "2_2") (pintype "passive"))
      (node (ref "C3") (pin "-") (pinfunction "-_-") (pintype "passive"))
      (node (ref "C4") (pin "-") (pinfunction "-_-") (pintype "passive"))
      (node (ref "GND") (pin "1") (pinfunction "1_1") (pintype "passive"))
      (node (ref "GND") (pin "10") (pinfunction "10_10") (pintype "passive"))
      (node (ref "GND") (pin "11") (pinfunction "11_11") (pintype "passive"))
      (node (ref "GND") (pin "12") (pinfunction "12_12") (pintype "passive"))
      (node (ref "GND") (pin "13") (pinfunction "13_13") (pintype "passive"))
      (node (ref "GND") (pin "14") (pinfunction "14_14") (pintype "passive"))
      (node (ref "GND") (pin "15") (pinfunction "15_15") (pintype "passive"))
      (node (ref "GND") (pin "16") (pinfunction "16_16") (pintype "passive"))
      (node (ref "GND") (pin "2") (pinfunction "2_2") (pintype "passive"))
      (node (ref "GND") (pin "3") (pinfunction "3_3") (pintype "passive"))
      (node (ref "GND") (pin "4") (pinfunction "4_4") (pintype "passive"))
      (node (ref "GND") (pin "5") (pinfunction "5_5") (pintype "passive"))
      (node (ref "GND") (pin "6") (pinfunction "6_6") (pintype "passive"))
      (node (ref "GND") (pin "7") (pinfunction "7_7") (pintype "passive"))
      (node (ref "GND") (pin "8") (pinfunction "8_8") (pintype "passive"))
      (node (ref "GND") (pin "9") (pinfunction "9_9") (pintype "passive"))
      (node (ref "IC2") (pin "2") (pinfunction "GND_2") (pintype "passive"))
      (node (ref "J1") (pin "1") (pinfunction "1_1") (pintype "passive"))
      (node (ref "R4") (pin "1") (pinfunction "1_1") (pintype "passive"))
    )
    (net (code "54") (name "Net-(IC2-VI)") (class "Default")
      (node (ref "+12") (pin "1") (pinfunction "1_1") (pintype "passive"))
      (node (ref "+12") (pin "10") (pinfunction "10_10") (pintype "passive"))
      (node (ref "+12") (pin "11") (pinfunction "11_11") (pintype "passive"))
      (node (ref "+12") (pin "12") (pinfunction "12_12") (pintype "passive"))
      (node (ref "+12") (pin "13") (pinfunction "13_13") (pintype "passive"))
      (node (ref "+12") (pin "14") (pinfunction "14_14") (pintype "passive"))
      (node (ref "+12") (pin "15") (pinfunction "15_15") (pintype "passive"))
      (node (ref "+12") (pin "16") (pinfunction "16_16") (pintype "passive"))
      (node (ref "+12") (pin "2") (pinfunction "2_2") (pintype "passive"))
      (node (ref "+12") (pin "3") (pinfunction "3_3") (pintype "passive"))
      (node (ref "+12") (pin "4") (pinfunction "4_4") (pintype "passive"))
      (node (ref "+12") (pin "5") (pinfunction "5_5") (pintype "passive"))
      (node (ref "+12") (pin "6") (pinfunction "6_6") (pintype "passive"))
      (node (ref "+12") (pin "7") (pinfunction "7_7") (pintype "passive"))
      (node (ref "+12") (pin "8") (pinfunction "8_8") (pintype "passive"))
      (node (ref "+12") (pin "9") (pinfunction "9_9") (pintype "passive"))
      (node (ref "C1") (pin "1") (pinfunction "1_1") (pintype "passive"))
      (node (ref "C3") (pin "+") (pinfunction "+_+") (pintype "passive"))
      (node (ref "IC2") (pin "1") (pinfunction "VI_1") (pintype "input"))
      (node (ref "J1") (pin "3") (pinfunction "3_3") (pintype "passive"))
    )
    (net (code "55") (name "Net-(IC2-VO)") (class "Default")
      (node (ref "+5") (pin "1") (pinfunction "1_1") (pintype "passive"))
      (node (ref "+5") (pin "10") (pinfunction "10_10") (pintype "passive"))
      (node (ref "+5") (pin "11") (pinfunction "11_11") (pintype "passive"))
      (node (ref "+5") (pin "12") (pinfunction "12_12") (pintype "passive"))
      (node (ref "+5") (pin "13") (pinfunction "13_13") (pintype "passive"))
      (node (ref "+5") (pin "14") (pinfunction "14_14") (pintype "passive"))
      (node (ref "+5") (pin "15") (pinfunction "15_15") (pintype "passive"))
      (node (ref "+5") (pin "16") (pinfunction "16_16") (pintype "passive"))
      (node (ref "+5") (pin "2") (pinfunction "2_2") (pintype "passive"))
      (node (ref "+5") (pin "3") (pinfunction "3_3") (pintype "passive"))
      (node (ref "+5") (pin "4") (pinfunction "4_4") (pintype "passive"))
      (node (ref "+5") (pin "5") (pinfunction "5_5") (pintype "passive"))
      (node (ref "+5") (pin "6") (pinfunction "6_6") (pintype "passive"))
      (node (ref "+5") (pin "7") (pinfunction "7_7") (pintype "passive"))
      (node (ref "+5") (pin "8") (pinfunction "8_8") (pintype "passive"))
      (node (ref "+5") (pin "9") (pinfunction "9_9") (pintype "passive"))
      (node (ref "C2") (pin "1") (pinfunction "1_1") (pintype "passive"))
      (node (ref "C4") (pin "+") (pinfunction "+_+") (pintype "passive"))
      (node (ref "IC2") (pin "3") (pinfunction "VO_3") (pintype "passive"))
      (node (ref "LED1") (pin "A") (pinfunction "A_A") (pintype "passive"))
    )
    (net (code "56") (name "Net-(IC3-GND)") (class "Default")
      (node (ref "G1") (pin "-") (pinfunction "-_-") (pintype "passive"))
      (node (ref "IC3") (pin "4") (pinfunction "GND_4") (pintype "power_in"))
      (node (ref "LSP22") (pin "MP") (pinfunction "MP_MP") (pintype "passive"))
    )
    (net (code "57") (name "Net-(IC3-SCL)") (class "Default")
      (node (ref "IC3") (pin "6") (pinfunction "SCL_6") (pintype "bidirectional"))
      (node (ref "JP1") (pin "2") (pinfunction "2_2") (pintype "passive"))
      (node (ref "R29") (pin "1") (pinfunction "1_1") (pintype "passive"))
    )
    (net (code "58") (name "Net-(IC3-SDA)") (class "Default")
      (node (ref "IC3") (pin "5") (pinfunction "SDA_5") (pintype "bidirectional"))
      (node (ref "JP1") (pin "1") (pinfunction "1_1") (pintype "passive"))
      (node (ref "R30") (pin "1") (pinfunction "1_1") (pintype "passive"))
    )
    (net (code "59") (name "Net-(IC3-SQW{slash}OUT)") (class "Default")
      (node (ref "IC3") (pin "7") (pinfunction "SQW/OUT_7") (pintype "bidirectional"))
      (node (ref "JP2") (pin "1") (pinfunction "1_1") (pintype "passive"))
    )
    (net (code "60") (name "Net-(IC3-VBAT)") (class "Default")
      (node (ref "G1") (pin "+") (pinfunction "+_+") (pintype "passive"))
      (node (ref "IC3") (pin "3") (pinfunction "VBAT_3") (pintype "power_in"))
    )
    (net (code "61") (name "Net-(IC3-VCC)") (class "Default")
      (node (ref "IC3") (pin "8") (pinfunction "VCC_8") (pintype "power_in"))
      (node (ref "LSP17") (pin "MP") (pinfunction "MP_MP") (pintype "passive"))
      (node (ref "R29") (pin "2") (pinfunction "2_2") (pintype "passive"))
      (node (ref "R30") (pin "2") (pinfunction "2_2") (pintype "passive"))
    )
    (net (code "62") (name "Net-(IC3-X1)") (class "Default")
      (node (ref "IC3") (pin "1") (pinfunction "X1_1") (pintype "passive"))
      (node (ref "Y2") (pin "1") (pinfunction "1_1") (pintype "passive"))
    )
    (net (code "63") (name "Net-(IC3-X2)") (class "Default")
      (node (ref "IC3") (pin "2") (pinfunction "X2_2") (pintype "passive"))
      (node (ref "Y2") (pin "2") (pinfunction "2_2") (pintype "passive"))
    )
    (net (code "64") (name "Net-(IO-OUT-Pad1)") (class "Default")
      (node (ref "IO-OUT") (pin "1") (pinfunction "1_1") (pintype "passive"))
      (node (ref "LED11") (pin "A") (pinfunction "A_A") (pintype "passive"))
    )
    (net (code "65") (name "Net-(IO-OUT-Pad2)") (class "Default")
      (node (ref "IO-OUT") (pin "2") (pinfunction "2_2") (pintype "passive"))
      (node (ref "LED10") (pin "A") (pinfunction "A_A") (pintype "passive"))
    )
    (net (code "66") (name "Net-(IO-OUT-Pad3)") (class "Default")
      (node (ref "IO-OUT") (pin "3") (pinfunction "3_3") (pintype "passive"))
      (node (ref "LED9") (pin "A") (pinfunction "A_A") (pintype "passive"))
    )
    (net (code "67") (name "Net-(IO-OUT-Pad4)") (class "Default")
      (node (ref "IO-OUT") (pin "4") (pinfunction "4_4") (pintype "passive"))
      (node (ref "LED8") (pin "A") (pinfunction "A_A") (pintype "passive"))
    )
    (net (code "68") (name "Net-(IO-OUT-Pad5)") (class "Default")
      (node (ref "IO-OUT") (pin "5") (pinfunction "5_5") (pintype "passive"))
      (node (ref "LED7") (pin "A") (pinfunction "A_A") (pintype "passive"))
    )
    (net (code "69") (name "Net-(IO-OUT-Pad6)") (class "Default")
      (node (ref "IO-OUT") (pin "6") (pinfunction "6_6") (pintype "passive"))
      (node (ref "LED6") (pin "A") (pinfunction "A_A") (pintype "passive"))
    )
    (net (code "70") (name "Net-(IO-OUT-Pad7)") (class "Default")
      (node (ref "IO-OUT") (pin "7") (pinfunction "7_7") (pintype "passive"))
      (node (ref "LED5") (pin "A") (pinfunction "A_A") (pintype "passive"))
    )
    (net (code "71") (name "Net-(IO-OUT-Pad8)") (class "Default")
      (node (ref "IO-OUT") (pin "8") (pinfunction "8_8") (pintype "passive"))
      (node (ref "LED4") (pin "A") (pinfunction "A_A") (pintype "passive"))
    )
    (net (code "72") (name "Net-(IO-OUT-Pad9)") (class "Default")
      (node (ref "IO-OUT") (pin "9") (pinfunction "9_9") (pintype "passive"))
      (node (ref "LED3") (pin "A") (pinfunction "A_A") (pintype "passive"))
    )
    (net (code "73") (name "Net-(IO-OUT-Pad10)") (class "Default")
      (node (ref "IO-OUT") (pin "10") (pinfunction "10_10") (pintype "passive"))
      (node (ref "LED2") (pin "A") (pinfunction "A_A") (pintype "passive"))
    )
    (net (code "74") (name "Net-(JP3-Pad1)") (class "Default")
      (node (ref "JP3") (pin "1") (pinfunction "1_1") (pintype "passive"))
      (node (ref "R15") (pin "1") (pinfunction "1_1") (pintype "passive"))
    )
    (net (code "75") (name "Net-(JP6-Pad1)") (class "Default")
      (node (ref "JP6") (pin "1") (pinfunction "1_1") (pintype "passive"))
      (node (ref "R16") (pin "1") (pinfunction "1_1") (pintype "passive"))
    )
    (net (code "76") (name "Net-(JP9-Pad1)") (class "Default")
      (node (ref "JP9") (pin "1") (pinfunction "1_1") (pintype "passive"))
      (node (ref "R17") (pin "1") (pinfunction "1_1") (pintype "passive"))
    )
    (net (code "77") (name "Net-(JP12-Pad1)") (class "Default")
      (node (ref "JP12") (pin "1") (pinfunction "1_1") (pintype "passive"))
      (node (ref "R18") (pin "1") (pinfunction "1_1") (pintype "passive"))
    )
    (net (code "78") (name "Net-(LED1-C)") (class "Default")
      (node (ref "LED1") (pin "K") (pinfunction "C_K") (pintype "passive"))
      (node (ref "R4") (pin "2") (pinfunction "2_2") (pintype "passive"))
    )
    (net (code "79") (name "Net-(LED2-C)") (class "Default")
      (node (ref "LED2") (pin "K") (pinfunction "C_K") (pintype "passive"))
      (node (ref "R5") (pin "1") (pinfunction "1_1") (pintype "passive"))
    )
    (net (code "80") (name "Net-(LED3-C)") (class "Default")
      (node (ref "LED3") (pin "K") (pinfunction "C_K") (pintype "passive"))
      (node (ref "R6") (pin "1") (pinfunction "1_1") (pintype "passive"))
    )
    (net (code "81") (name "Net-(LED4-C)") (class "Default")
      (node (ref "LED4") (pin "K") (pinfunction "C_K") (pintype "passive"))
      (node (ref "R7") (pin "1") (pinfunction "1_1") (pintype "passive"))
    )
    (net (code "82") (name "Net-(LED5-C)") (class "Default")
      (node (ref "LED5") (pin "K") (pinfunction "C_K") (pintype "passive"))
      (node (ref "R8") (pin "1") (pinfunction "1_1") (pintype "passive"))
    )
    (net (code "83") (name "Net-(LED6-C)") (class "Default")
      (node (ref "LED6") (pin "K") (pinfunction "C_K") (pintype "passive"))
      (node (ref "R9") (pin "1") (pinfunction "1_1") (pintype "passive"))
    )
    (net (code "84") (name "Net-(LED7-C)") (class "Default")
      (node (ref "LED7") (pin "K") (pinfunction "C_K") (pintype "passive"))
      (node (ref "R10") (pin "1") (pinfunction "1_1") (pintype "passive"))
    )
    (net (code "85") (name "Net-(LED8-C)") (class "Default")
      (node (ref "LED8") (pin "K") (pinfunction "C_K") (pintype "passive"))
      (node (ref "R11") (pin "1") (pinfunction "1_1") (pintype "passive"))
    )
    (net (code "86") (name "Net-(LED9-C)") (class "Default")
      (node (ref "LED9") (pin "K") (pinfunction "C_K") (pintype "passive"))
      (node (ref "R12") (pin "1") (pinfunction "1_1") (pintype "passive"))
    )
    (net (code "87") (name "Net-(LED10-C)") (class "Default")
      (node (ref "LED10") (pin "K") (pinfunction "C_K") (pintype "passive"))
      (node (ref "R13") (pin "1") (pinfunction "1_1") (pintype "passive"))
    )
    (net (code "88") (name "Net-(LED11-C)") (class "Default")
      (node (ref "LED11") (pin "K") (pinfunction "C_K") (pintype "passive"))
      (node (ref "R14") (pin "1") (pinfunction "1_1") (pintype "passive"))
    )
    (net (code "89") (name "Net-(LSP15-PadMP)") (class "Default")
      (node (ref "LSP15") (pin "MP") (pinfunction "MP_MP") (pintype "passive"))
      (node (ref "R19") (pin "2") (pinfunction "2_2") (pintype "passive"))
      (node (ref "R20") (pin "2") (pinfunction "2_2") (pintype "passive"))
      (node (ref "R21") (pin "2") (pinfunction "2_2") (pintype "passive"))
      (node (ref "R22") (pin "2") (pinfunction "2_2") (pintype "passive"))
      (node (ref "R23") (pin "2") (pinfunction "2_2") (pintype "passive"))
      (node (ref "R24") (pin "2") (pinfunction "2_2") (pintype "passive"))
    )
    (net (code "90") (name "Net-(LSP18-PadMP)") (class "Default")
      (node (ref "LSP18") (pin "MP") (pinfunction "MP_MP") (pintype "passive"))
      (node (ref "R10") (pin "2") (pinfunction "2_2") (pintype "passive"))
      (node (ref "R11") (pin "2") (pinfunction "2_2") (pintype "passive"))
      (node (ref "R12") (pin "2") (pinfunction "2_2") (pintype "passive"))
      (node (ref "R13") (pin "2") (pinfunction "2_2") (pintype "passive"))
      (node (ref "R14") (pin "2") (pinfunction "2_2") (pintype "passive"))
      (node (ref "R5") (pin "2") (pinfunction "2_2") (pintype "passive"))
      (node (ref "R6") (pin "2") (pinfunction "2_2") (pintype "passive"))
      (node (ref "R7") (pin "2") (pinfunction "2_2") (pintype "passive"))
      (node (ref "R8") (pin "2") (pinfunction "2_2") (pintype "passive"))
      (node (ref "R9") (pin "2") (pinfunction "2_2") (pintype "passive"))
    )
    (net (code "91") (name "Net-(OK1-A)") (class "Default")
      (node (ref "JP18") (pin "1") (pinfunction "1_1") (pintype "passive"))
      (node (ref "OK1") (pin "1") (pinfunction "A_1") (pintype "passive"))
    )
    (net (code "92") (name "Net-(OK1-A1)") (class "Default")
      (node (ref "LSP4") (pin "MP") (pinfunction "MP_MP") (pintype "passive"))
      (node (ref "OK1") (pin "4") (pinfunction "A1_4") (pintype "passive"))
    )
    (net (code "93") (name "Net-(OK1-A2)") (class "Default")
      (node (ref "LSP3") (pin "MP") (pinfunction "MP_MP") (pintype "passive"))
      (node (ref "OK1") (pin "6") (pinfunction "A2_6") (pintype "passive"))
    )
    (net (code "94") (name "Net-(OK1-C)") (class "Default")
      (node (ref "OK1") (pin "2") (pinfunction "C_2") (pintype "passive"))
      (node (ref "R20") (pin "1") (pinfunction "1_1") (pintype "passive"))
    )
    (net (code "95") (name "Net-(OK2-A)") (class "Default")
      (node (ref "JP19") (pin "1") (pinfunction "1_1") (pintype "passive"))
      (node (ref "OK2") (pin "1") (pinfunction "A_1") (pintype "passive"))
    )
    (net (code "96") (name "Net-(OK2-A1)") (class "Default")
      (node (ref "LSP6") (pin "MP") (pinfunction "MP_MP") (pintype "passive"))
      (node (ref "OK2") (pin "4") (pinfunction "A1_4") (pintype "passive"))
    )
    (net (code "97") (name "Net-(OK2-A2)") (class "Default")
      (node (ref "LSP5") (pin "MP") (pinfunction "MP_MP") (pintype "passive"))
      (node (ref "OK2") (pin "6") (pinfunction "A2_6") (pintype "passive"))
    )
    (net (code "98") (name "Net-(OK2-C)") (class "Default")
      (node (ref "OK2") (pin "2") (pinfunction "C_2") (pintype "passive"))
      (node (ref "R21") (pin "1") (pinfunction "1_1") (pintype "passive"))
    )
    (net (code "99") (name "Net-(OK3-A)") (class "Default")
      (node (ref "JP21") (pin "1") (pinfunction "1_1") (pintype "passive"))
      (node (ref "OK3") (pin "1") (pinfunction "A_1") (pintype "passive"))
    )
    (net (code "100") (name "Net-(OK3-A1)") (class "Default")
      (node (ref "LSP10") (pin "MP") (pinfunction "MP_MP") (pintype "passive"))
      (node (ref "OK3") (pin "4") (pinfunction "A1_4") (pintype "passive"))
    )
    (net (code "101") (name "Net-(OK3-A2)") (class "Default")
      (node (ref "LSP9") (pin "MP") (pinfunction "MP_MP") (pintype "passive"))
      (node (ref "OK3") (pin "6") (pinfunction "A2_6") (pintype "passive"))
    )
    (net (code "102") (name "Net-(OK3-C)") (class "Default")
      (node (ref "OK3") (pin "2") (pinfunction "C_2") (pintype "passive"))
      (node (ref "R23") (pin "1") (pinfunction "1_1") (pintype "passive"))
    )
    (net (code "103") (name "Net-(OK4-A)") (class "Default")
      (node (ref "JP20") (pin "1") (pinfunction "1_1") (pintype "passive"))
      (node (ref "OK4") (pin "1") (pinfunction "A_1") (pintype "passive"))
    )
    (net (code "104") (name "Net-(OK4-A1)") (class "Default")
      (node (ref "LSP8") (pin "MP") (pinfunction "MP_MP") (pintype "passive"))
      (node (ref "OK4") (pin "4") (pinfunction "A1_4") (pintype "passive"))
    )
    (net (code "105") (name "Net-(OK4-A2)") (class "Default")
      (node (ref "LSP7") (pin "MP") (pinfunction "MP_MP") (pintype "passive"))
      (node (ref "OK4") (pin "6") (pinfunction "A2_6") (pintype "passive"))
    )
    (net (code "106") (name "Net-(OK4-C)") (class "Default")
      (node (ref "OK4") (pin "2") (pinfunction "C_2") (pintype "passive"))
      (node (ref "R24") (pin "1") (pinfunction "1_1") (pintype "passive"))
    )
    (net (code "107") (name "Net-(OK5-A)") (class "Default")
      (node (ref "JP17") (pin "1") (pinfunction "1_1") (pintype "passive"))
      (node (ref "OK5") (pin "1") (pinfunction "A_1") (pintype "passive"))
    )
    (net (code "108") (name "Net-(OK5-A1)") (class "Default")
      (node (ref "LSP2") (pin "MP") (pinfunction "MP_MP") (pintype "passive"))
      (node (ref "OK5") (pin "4") (pinfunction "A1_4") (pintype "passive"))
    )
    (net (code "109") (name "Net-(OK5-A2)") (class "Default")
      (node (ref "LSP1") (pin "MP") (pinfunction "MP_MP") (pintype "passive"))
      (node (ref "OK5") (pin "6") (pinfunction "A2_6") (pintype "passive"))
    )
    (net (code "110") (name "Net-(OK5-C)") (class "Default")
      (node (ref "OK5") (pin "2") (pinfunction "C_2") (pintype "passive"))
      (node (ref "R19") (pin "1") (pinfunction "1_1") (pintype "passive"))
    )
    (net (code "111") (name "Net-(OK6-A)") (class "Default")
      (node (ref "JP16") (pin "1") (pinfunction "1_1") (pintype "passive"))
      (node (ref "OK6") (pin "1") (pinfunction "A_1") (pintype "passive"))
    )
    (net (code "112") (name "Net-(OK6-A1)") (class "Default")
      (node (ref "LSP12") (pin "MP") (pinfunction "MP_MP") (pintype "passive"))
      (node (ref "OK6") (pin "4") (pinfunction "A1_4") (pintype "passive"))
    )
    (net (code "113") (name "Net-(OK6-A2)") (class "Default")
      (node (ref "LSP11") (pin "MP") (pinfunction "MP_MP") (pintype "passive"))
      (node (ref "OK6") (pin "6") (pinfunction "A2_6") (pintype "passive"))
    )
    (net (code "114") (name "Net-(OK6-C)") (class "Default")
      (node (ref "OK6") (pin "2") (pinfunction "C_2") (pintype "passive"))
      (node (ref "R22") (pin "1") (pinfunction "1_1") (pintype "passive"))
    )
    (net (code "115") (name "Net-(Q1-D)") (class "Default")
      (node (ref "JP4") (pin "2") (pinfunction "2_2") (pintype "passive"))
      (node (ref "JP5") (pin "1") (pinfunction "1_1") (pintype "passive"))
      (node (ref "Q1") (pin "2") (pinfunction "D_2") (pintype "passive"))
    )
    (net (code "116") (name "Net-(Q1-G)") (class "Default")
      (node (ref "Q1") (pin "1") (pinfunction "G_1") (pintype "passive"))
      (node (ref "R15") (pin "2") (pinfunction "2_2") (pintype "passive"))
    )
    (net (code "117") (name "Net-(Q1-S)") (class "Default")
      (node (ref "LSP14") (pin "MP") (pinfunction "MP_MP") (pintype "passive"))
      (node (ref "Q1") (pin "3") (pinfunction "S_3") (pintype "passive"))
      (node (ref "Q2") (pin "3") (pinfunction "S_3") (pintype "passive"))
      (node (ref "Q3") (pin "3") (pinfunction "S_3") (pintype "passive"))
      (node (ref "Q4") (pin "3") (pinfunction "S_3") (pintype "passive"))
    )
    (net (code "118") (name "Net-(Q2-D)") (class "Default")
      (node (ref "JP7") (pin "2") (pinfunction "2_2") (pintype "passive"))
      (node (ref "JP8") (pin "1") (pinfunction "1_1") (pintype "passive"))
      (node (ref "Q2") (pin "2") (pinfunction "D_2") (pintype "passive"))
    )
    (net (code "119") (name "Net-(Q2-G)") (class "Default")
      (node (ref "Q2") (pin "1") (pinfunction "G_1") (pintype "passive"))
      (node (ref "R16") (pin "2") (pinfunction "2_2") (pintype "passive"))
    )
    (net (code "120") (name "Net-(Q3-D)") (class "Default")
      (node (ref "JP10") (pin "2") (pinfunction "2_2") (pintype "passive"))
      (node (ref "JP11") (pin "1") (pinfunction "1_1") (pintype "passive"))
      (node (ref "Q3") (pin "2") (pinfunction "D_2") (pintype "passive"))
    )
    (net (code "121") (name "Net-(Q3-G)") (class "Default")
      (node (ref "Q3") (pin "1") (pinfunction "G_1") (pintype "passive"))
      (node (ref "R17") (pin "2") (pinfunction "2_2") (pintype "passive"))
    )
    (net (code "122") (name "Net-(Q4-D)") (class "Default")
      (node (ref "JP13") (pin "2") (pinfunction "2_2") (pintype "passive"))
      (node (ref "JP14") (pin "1") (pinfunction "1_1") (pintype "passive"))
      (node (ref "Q4") (pin "2") (pinfunction "D_2") (pintype "passive"))
    )
    (net (code "123") (name "Net-(Q4-G)") (class "Default")
      (node (ref "Q4") (pin "1") (pinfunction "G_1") (pintype "passive"))
      (node (ref "R18") (pin "2") (pinfunction "2_2") (pintype "passive"))
    )
    (net (code "124") (name "Net-(R2-A)") (class "Default")
      (node (ref "DSPHD44780") (pin "1") (pinfunction "1_1") (pintype "passive"))
      (node (ref "LSP20") (pin "MP") (pinfunction "MP_MP") (pintype "passive"))
      (node (ref "R2") (pin "1") (pinfunction "A_1") (pintype "passive"))
      (node (ref "R3") (pin "2") (pinfunction "2_2") (pintype "passive"))
    )
    (net (code "125") (name "Net-(R2-E)") (class "Default")
      (node (ref "DSPHD44780") (pin "10") (pinfunction "10_10") (pintype "passive"))
      (node (ref "DSPHD44780") (pin "16") (pinfunction "16_16") (pintype "passive"))
      (node (ref "DSPHD44780") (pin "2") (pinfunction "2_2") (pintype "passive"))
      (node (ref "DSPHD44780") (pin "7") (pinfunction "7_7") (pintype "passive"))
      (node (ref "DSPHD44780") (pin "8") (pinfunction "8_8") (pintype "passive"))
      (node (ref "DSPHD44780") (pin "9") (pinfunction "9_9") (pintype "passive"))
      (node (ref "LSP19") (pin "MP") (pinfunction "MP_MP") (pintype "passive"))
      (node (ref "R2") (pin "3") (pinfunction "E_3") (pintype "passive"))
    )
    (net (code "126") (name "Net-(R2-S)") (class "Default")
      (node (ref "DSPHD44780") (pin "3") (pinfunction "3_3") (pintype "passive"))
      (node (ref "R2") (pin "2") (pinfunction "S_2") (pintype "passive"))
    )
    (net (code "127") (name "Net-(R25-A)") (class "Default")
      (node (ref "LSP21") (pin "MP") (pinfunction "MP_MP") (pintype "passive"))
      (node (ref "R25") (pin "1") (pinfunction "A_1") (pintype "passive"))
      (node (ref "R26") (pin "1") (pinfunction "A_1") (pintype "passive"))
      (node (ref "R27") (pin "1") (pinfunction "A_1") (pintype "passive"))
      (node (ref "R28") (pin "1") (pinfunction "A_1") (pintype "passive"))
    )
    (net (code "128") (name "Net-(R25-E)") (class "Default")
      (node (ref "LSP16") (pin "MP") (pinfunction "MP_MP") (pintype "passive"))
      (node (ref "R25") (pin "3") (pinfunction "E_3") (pintype "passive"))
      (node (ref "R26") (pin "3") (pinfunction "E_3") (pintype "passive"))
      (node (ref "R27") (pin "3") (pinfunction "E_3") (pintype "passive"))
      (node (ref "R28") (pin "3") (pinfunction "E_3") (pintype "passive"))
    )
    (net (code "129") (name "Net-(R25-S)") (class "Default")
      (node (ref "R25") (pin "2") (pinfunction "S_2") (pintype "passive"))
      (node (ref "RC1") (pin "1") (pinfunction "1_1") (pintype "passive"))
    )
    (net (code "130") (name "Net-(R26-S)") (class "Default")
      (node (ref "R26") (pin "2") (pinfunction "S_2") (pintype "passive"))
      (node (ref "RC6") (pin "1") (pinfunction "1_1") (pintype "passive"))
    )
    (net (code "131") (name "Net-(R27-S)") (class "Default")
      (node (ref "R27") (pin "2") (pinfunction "S_2") (pintype "passive"))
      (node (ref "RC7") (pin "1") (pinfunction "1_1") (pintype "passive"))
    )
    (net (code "132") (name "Net-(R28-S)") (class "Default")
      (node (ref "R28") (pin "2") (pinfunction "S_2") (pintype "passive"))
      (node (ref "RC8") (pin "1") (pinfunction "1_1") (pintype "passive"))
    )
    (net (code "133") (name "unconnected-(G1-+-Pad+@1)") (class "Default")
      (node (ref "G1") (pin "+@1") (pinfunction "+_+@1") (pintype "passive"))
    )
    (net (code "134") (name "unconnected-(ICSP-Pad2)") (class "Default")
      (node (ref "ICSP") (pin "2") (pinfunction "2_2") (pintype "passive"))
    )
    (net (code "135") (name "unconnected-(ICSP-Pad6)") (class "Default")
      (node (ref "ICSP") (pin "6") (pinfunction "6_6") (pintype "passive"))
    )
    (net (code "136") (name "unconnected-(J1-Pad2)") (class "Default")
      (node (ref "J1") (pin "2") (pinfunction "2_2") (pintype "passive"))
    )
    (net (code "137") (name "unconnected-(USB-Pad1)") (class "Default")
      (node (ref "USB") (pin "1") (pinfunction "1_1") (pintype "passive"))
    )
    (net (code "138") (name "unconnected-(USB-Pad5)") (class "Default")
      (node (ref "USB") (pin "5") (pinfunction "5_5") (pintype "passive"))
    )
  )
)
